# ESP32_EDITED.net
KiCad netlist of a schematic drawn in Altium Designer
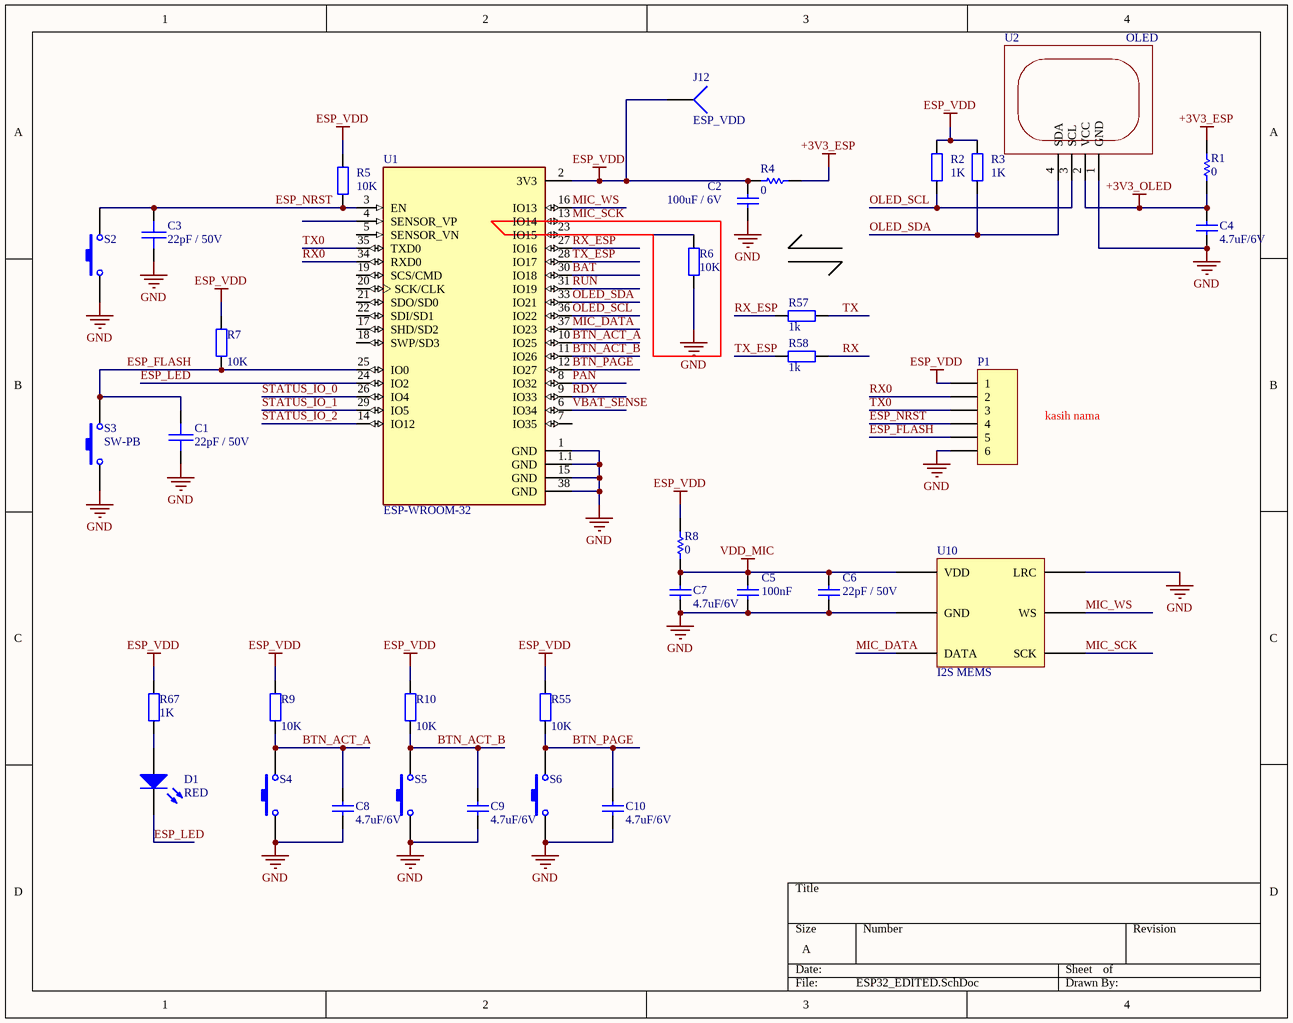
[diagram p0: ESP32_EDITED.SchDoc]

(export (version "E")
  (design (tool "Eeschema 10.0.6"))
  (components
    (comp (ref "C1")
      (value "22pF / 50V")
      (footprint "CR2012-0805")
      (description "Surface mount capacitor 0402")
      (libsource (lib "Vowstar_Basic_Device") (part "SMT_C_0402"))
    )
    (comp (ref "C2")
      (value "100uF / 6V")
      (footprint "CR3216-1206")
      (description "Capacitor")
      (fields (field (name "PUBLISHER") "Altium Limited"))
      (libsource (lib "Miscellaneous Devices") (part "Cap"))
    )
    (comp (ref "C3")
      (value "22pF / 50V")
      (footprint "CR2012-0805")
      (description "Surface mount capacitor 0402")
      (libsource (lib "Vowstar_Basic_Device") (part "SMT_C_0402"))
    )
    (comp (ref "C4")
      (value "4.7uF/6V")
      (footprint "CR2012-0805")
      (description "Capacitor (Semiconductor SIM Model)")
      (fields (field (name "PUBLISHER") "Altium Limited"))
      (libsource (lib "passive") (part "Cap Semi"))
    )
    (comp (ref "C5")
      (value "100nF")
      (footprint "CR2012-0805")
      (description "Capacitor")
      (fields (field (name "PUBLISHER") "Altium Limited"))
      (libsource (lib "Miscellaneous Devices") (part "Cap"))
    )
    (comp (ref "C6")
      (value "22pF / 50V")
      (footprint "CR2012-0805")
      (description "Capacitor")
      (fields (field (name "PUBLISHER") "Altium Limited"))
      (libsource (lib "Miscellaneous Devices") (part "Cap"))
    )
    (comp (ref "C7")
      (value "4.7uF/6V")
      (footprint "CR2012-0805")
      (description "Capacitor (Semiconductor SIM Model)")
      (fields (field (name "PUBLISHER") "Altium Limited"))
      (libsource (lib "passive") (part "Cap Semi"))
    )
    (comp (ref "C8")
      (value "4.7uF/6V")
      (footprint "CR2012-0805")
      (description "Capacitor (Semiconductor SIM Model)")
      (fields (field (name "PUBLISHER") "Altium Limited"))
      (libsource (lib "passive") (part "Cap Semi"))
    )
    (comp (ref "C9")
      (value "4.7uF/6V")
      (footprint "CR2012-0805")
      (description "Capacitor (Semiconductor SIM Model)")
      (fields (field (name "PUBLISHER") "Altium Limited"))
      (libsource (lib "passive") (part "Cap Semi"))
    )
    (comp (ref "C10")
      (value "4.7uF/6V")
      (footprint "CR2012-0805")
      (description "Capacitor (Semiconductor SIM Model)")
      (fields (field (name "PUBLISHER") "Altium Limited"))
      (libsource (lib "passive") (part "Cap Semi"))
    )
    (comp (ref "D1")
      (value "RED")
      (footprint "LED1206")
      (description "Typical RED, GREEN, YELLOW, AMBER GaAs LED")
      (fields (field (name "PUBLISHER") "Altium Limited"))
      (libsource (lib "Miscellaneous Devices") (part "LED2"))
    )
    (comp (ref "J12")
      (value "ESP_VDD")
      (footprint "PIN1")
      (description "Socket")
      (fields (field (name "PUBLISHER") "Altium Limited"))
      (libsource (lib "Miscellaneous Connectors") (part "Socket"))
    )
    (comp (ref "P1")
      (value "Header 6")
      (footprint "HDR1X6")
      (description "Header, 6-Pin")
      (fields (field (name "PUBLISHER") "Altium Limited"))
      (libsource (lib "Miscellaneous Connectors") (part "Header 6"))
    )
    (comp (ref "R1")
      (value "0")
      (footprint "JP1_SMD")
      (description "Semiconductor Resistor")
      (fields (field (name "PUBLISHER") "Altium Limited"))
      (libsource (lib "passive") (part "Res Semi"))
    )
    (comp (ref "R2")
      (value "1K")
      (footprint "CR2012-0805")
      (description "Resistor")
      (fields (field (name "PUBLISHER") "Altium Limited"))
      (libsource (lib "Miscellaneous Devices") (part "Res2"))
    )
    (comp (ref "R3")
      (value "1K")
      (footprint "CR2012-0805")
      (description "Resistor")
      (fields (field (name "PUBLISHER") "Altium Limited"))
      (libsource (lib "Miscellaneous Devices") (part "Res2"))
    )
    (comp (ref "R4")
      (value "0")
      (footprint "JP1_SMD")
      (description "Semiconductor Resistor")
      (fields (field (name "PUBLISHER") "Altium Limited"))
      (libsource (lib "passive") (part "Res Semi"))
    )
    (comp (ref "R5")
      (value "10K")
      (footprint "CR2012-0805")
      (description "Resistor")
      (fields (field (name "PUBLISHER") "Altium Limited"))
      (libsource (lib "Miscellaneous Devices") (part "Res2"))
    )
    (comp (ref "R6")
      (value "10K")
      (footprint "CR2012-0805")
      (description "Resistor")
      (fields (field (name "PUBLISHER") "Altium Limited"))
      (libsource (lib "") (part "Res2_2"))
    )
    (comp (ref "R7")
      (value "10K")
      (footprint "CR2012-0805")
      (description "Resistor")
      (fields (field (name "PUBLISHER") "Altium Limited"))
      (libsource (lib "Miscellaneous Devices") (part "Res2"))
    )
    (comp (ref "R8")
      (value "0")
      (footprint "JP1_SMD")
      (description "Semiconductor Resistor")
      (fields (field (name "PUBLISHER") "Altium Limited"))
      (libsource (lib "passive") (part "Res Semi"))
    )
    (comp (ref "R9")
      (value "10K")
      (footprint "CR2012-0805")
      (description "Resistor")
      (fields (field (name "PUBLISHER") "Altium Limited"))
      (libsource (lib "Miscellaneous Devices") (part "Res2"))
    )
    (comp (ref "R10")
      (value "10K")
      (footprint "CR2012-0805")
      (description "Resistor")
      (fields (field (name "PUBLISHER") "Altium Limited"))
      (libsource (lib "Miscellaneous Devices") (part "Res2"))
    )
    (comp (ref "R55")
      (value "10K")
      (footprint "CR2012-0805")
      (description "Resistor")
      (fields (field (name "PUBLISHER") "Altium Limited"))
      (libsource (lib "Miscellaneous Devices") (part "Res2"))
    )
    (comp (ref "R57")
      (value "1k")
      (footprint "CR2012-0805")
      (description "Resistor")
      (fields (field (name "PUBLISHER") "Altium Limited"))
      (libsource (lib "") (part "Res2_1"))
    )
    (comp (ref "R58")
      (value "1k")
      (footprint "CR2012-0805")
      (description "Resistor")
      (fields (field (name "PUBLISHER") "Altium Limited"))
      (libsource (lib "") (part "Res2_1"))
    )
    (comp (ref "R67")
      (value "1K")
      (footprint "CR2012-0805")
      (description "Resistor")
      (fields (field (name "PUBLISHER") "Altium Limited"))
      (libsource (lib "Miscellaneous Devices") (part "Res2"))
    )
    (comp (ref "S2")
      (value "SW-PB")
      (footprint "pushbutton")
      (description "Switch")
      (fields (field (name "PUBLISHER") "Altium Limited"))
      (libsource (lib "Miscellaneous Devices") (part "SW-PB"))
    )
    (comp (ref "S3") (value "SW-PB") (footprint "pushbutton") (libsource (lib "passive") (part "pushbutton")))
    (comp (ref "S4")
      (value "SW-PB")
      (footprint "pushbutton")
      (description "Switch")
      (fields (field (name "PUBLISHER") "Altium Limited"))
      (libsource (lib "Miscellaneous Devices") (part "SW-PB"))
    )
    (comp (ref "S5")
      (value "SW-PB")
      (footprint "pushbutton")
      (description "Switch")
      (fields (field (name "PUBLISHER") "Altium Limited"))
      (libsource (lib "Miscellaneous Devices") (part "SW-PB"))
    )
    (comp (ref "S6")
      (value "SW-PB")
      (footprint "pushbutton")
      (description "Switch")
      (fields (field (name "PUBLISHER") "Altium Limited"))
      (libsource (lib "Miscellaneous Devices") (part "SW-PB"))
    )
    (comp (ref "U1")
      (value "ESP-WROOM-32")
      (footprint "MODULE_ESP-WROOM-32")
      (description "WiFi 802.11b/g/n/d/e/i Transceiver Module 2.4GHz Surface Mount")
      (fields (field (name "MF") "Olimex LTD"))
      (libsource (lib "ESP-WROOM-32") (part "ESP-WROOM-32"))
    )
    (comp (ref "U2")
      (value "OLED")
      (footprint "OLED_Display_1in6")
      (description "I2C OLED 0.96\"")
      (libsource (lib "active") (part "OLED"))
    )
    (comp (ref "U10") (value "I2S MEMS") (footprint "INMP441") (libsource (lib "active") (part "INMP441")))
  )
  (nets
    (net (code "1") (name "+3V3_ESP") (class "Default")
      (node (ref "R1") (pin "2") (pinfunction "2_2") (pintype "passive"))
      (node (ref "R4") (pin "2") (pinfunction "2_2") (pintype "passive"))
    )
    (net (code "2") (name "+3V3_OLED") (class "Default")
      (node (ref "C4") (pin "2") (pinfunction "2_2") (pintype "passive"))
      (node (ref "R1") (pin "1") (pinfunction "1_1") (pintype "passive"))
      (node (ref "U2") (pin "2") (pinfunction "VCC_2") (pintype "passive"))
    )
    (net (code "3") (name "/BAT") (class "Default")
      (node (ref "U1") (pin "30") (pinfunction "IO18_30") (pintype "bidirectional"))
    )
    (net (code "4") (name "/BTN_ACT_A") (class "Default")
      (node (ref "C8") (pin "2") (pinfunction "2_2") (pintype "passive"))
      (node (ref "R9") (pin "1") (pinfunction "1_1") (pintype "passive"))
      (node (ref "S4") (pin "2") (pinfunction "2_2") (pintype "passive"))
      (node (ref "U1") (pin "10") (pinfunction "IO25_10") (pintype "bidirectional"))
    )
    (net (code "5") (name "/BTN_ACT_B") (class "Default")
      (node (ref "C9") (pin "2") (pinfunction "2_2") (pintype "passive"))
      (node (ref "R10") (pin "1") (pinfunction "1_1") (pintype "passive"))
      (node (ref "S5") (pin "2") (pinfunction "2_2") (pintype "passive"))
      (node (ref "U1") (pin "11") (pinfunction "IO26_11") (pintype "bidirectional"))
    )
    (net (code "6") (name "/BTN_PAGE") (class "Default")
      (node (ref "C10") (pin "2") (pinfunction "2_2") (pintype "passive"))
      (node (ref "R55") (pin "1") (pinfunction "1_1") (pintype "passive"))
      (node (ref "S6") (pin "2") (pinfunction "2_2") (pintype "passive"))
      (node (ref "U1") (pin "12") (pinfunction "IO27_12") (pintype "bidirectional"))
    )
    (net (code "7") (name "/ESP_FLASH") (class "Default")
      (node (ref "C1") (pin "1") (pinfunction "1_1") (pintype "passive"))
      (node (ref "P1") (pin "5") (pinfunction "5_5") (pintype "passive"))
      (node (ref "R7") (pin "1") (pinfunction "1_1") (pintype "passive"))
      (node (ref "S3") (pin "2") (pinfunction "2_2") (pintype "passive"))
      (node (ref "U1") (pin "25") (pinfunction "IO0_25") (pintype "bidirectional"))
    )
    (net (code "8") (name "/ESP_LED") (class "Default")
      (node (ref "D1") (pin "K") (pinfunction "K_K") (pintype "passive"))
      (node (ref "U1") (pin "24") (pinfunction "IO2_24") (pintype "bidirectional"))
    )
    (net (code "9") (name "/ESP_NRST") (class "Default")
      (node (ref "C3") (pin "1") (pinfunction "1_1") (pintype "passive"))
      (node (ref "P1") (pin "4") (pinfunction "4_4") (pintype "passive"))
      (node (ref "R5") (pin "1") (pinfunction "1_1") (pintype "passive"))
      (node (ref "S2") (pin "2") (pinfunction "2_2") (pintype "passive"))
      (node (ref "U1") (pin "3") (pinfunction "EN_3") (pintype "input"))
    )
    (net (code "10") (name "/MIC_DATA") (class "Default")
      (node (ref "U1") (pin "37") (pinfunction "IO23_37") (pintype "bidirectional"))
      (node (ref "U10") (pin "6") (pinfunction "DATA_6") (pintype "passive"))
    )
    (net (code "11") (name "/MIC_SCK") (class "Default")
      (node (ref "U1") (pin "13") (pinfunction "IO14_13") (pintype "bidirectional"))
      (node (ref "U10") (pin "1") (pinfunction "SCK_1") (pintype "passive"))
    )
    (net (code "12") (name "/MIC_WS") (class "Default")
      (node (ref "U1") (pin "16") (pinfunction "IO13_16") (pintype "bidirectional"))
      (node (ref "U10") (pin "2") (pinfunction "WS_2") (pintype "passive"))
    )
    (net (code "13") (name "/OLED_SCL") (class "Default")
      (node (ref "R2") (pin "1") (pinfunction "1_1") (pintype "passive"))
      (node (ref "U1") (pin "36") (pinfunction "IO22_36") (pintype "bidirectional"))
      (node (ref "U2") (pin "3") (pinfunction "SCL_3") (pintype "passive"))
    )
    (net (code "14") (name "/OLED_SDA") (class "Default")
      (node (ref "R3") (pin "1") (pinfunction "1_1") (pintype "passive"))
      (node (ref "U1") (pin "33") (pinfunction "IO21_33") (pintype "bidirectional"))
      (node (ref "U2") (pin "4") (pinfunction "SDA_4") (pintype "passive"))
    )
    (net (code "15") (name "/PAN") (class "Default")
      (node (ref "U1") (pin "8") (pinfunction "IO32_8") (pintype "bidirectional"))
    )
    (net (code "16") (name "/RDY") (class "Default")
      (node (ref "U1") (pin "9") (pinfunction "IO33_9") (pintype "bidirectional"))
    )
    (net (code "17") (name "/RUN") (class "Default")
      (node (ref "U1") (pin "31") (pinfunction "IO19_31") (pintype "bidirectional"))
    )
    (net (code "18") (name "/RX") (class "Default")
      (node (ref "R58") (pin "1") (pinfunction "1_1") (pintype "passive"))
    )
    (net (code "19") (name "/RX0") (class "Default")
      (node (ref "P1") (pin "2") (pinfunction "2_2") (pintype "passive"))
      (node (ref "U1") (pin "34") (pinfunction "RXD0_34") (pintype "bidirectional"))
    )
    (net (code "20") (name "/RX_ESP") (class "Default")
      (node (ref "R57") (pin "2") (pinfunction "2_2") (pintype "passive"))
      (node (ref "U1") (pin "27") (pinfunction "IO16_27") (pintype "bidirectional"))
    )
    (net (code "21") (name "/STATUS_IO_0") (class "Default")
      (node (ref "U1") (pin "26") (pinfunction "IO4_26") (pintype "bidirectional"))
    )
    (net (code "22") (name "/STATUS_IO_1") (class "Default")
      (node (ref "U1") (pin "29") (pinfunction "IO5_29") (pintype "bidirectional"))
    )
    (net (code "23") (name "/STATUS_IO_2") (class "Default")
      (node (ref "U1") (pin "14") (pinfunction "IO12_14") (pintype "bidirectional"))
    )
    (net (code "24") (name "/TX") (class "Default")
      (node (ref "R57") (pin "1") (pinfunction "1_1") (pintype "passive"))
    )
    (net (code "25") (name "/TX0") (class "Default")
      (node (ref "P1") (pin "3") (pinfunction "3_3") (pintype "passive"))
      (node (ref "U1") (pin "35") (pinfunction "TXD0_35") (pintype "bidirectional"))
    )
    (net (code "26") (name "/TX_ESP") (class "Default")
      (node (ref "R58") (pin "2") (pinfunction "2_2") (pintype "passive"))
      (node (ref "U1") (pin "28") (pinfunction "IO17_28") (pintype "bidirectional"))
    )
    (net (code "27") (name "/VBAT_SENSE") (class "Default")
      (node (ref "U1") (pin "6") (pinfunction "IO34_6") (pintype "bidirectional"))
    )
    (net (code "28") (name "ESP_VDD") (class "Default")
      (node (ref "C2") (pin "2") (pinfunction "2_2") (pintype "passive"))
      (node (ref "J12") (pin "1") (pinfunction "1_1") (pintype "passive"))
      (node (ref "P1") (pin "1") (pinfunction "1_1") (pintype "passive"))
      (node (ref "R10") (pin "2") (pinfunction "2_2") (pintype "passive"))
      (node (ref "R2") (pin "2") (pinfunction "2_2") (pintype "passive"))
      (node (ref "R3") (pin "2") (pinfunction "2_2") (pintype "passive"))
      (node (ref "R4") (pin "1") (pinfunction "1_1") (pintype "passive"))
      (node (ref "R5") (pin "2") (pinfunction "2_2") (pintype "passive"))
      (node (ref "R55") (pin "2") (pinfunction "2_2") (pintype "passive"))
      (node (ref "R67") (pin "2") (pinfunction "2_2") (pintype "passive"))
      (node (ref "R7") (pin "2") (pinfunction "2_2") (pintype "passive"))
      (node (ref "R8") (pin "1") (pinfunction "1_1") (pintype "passive"))
      (node (ref "R9") (pin "2") (pinfunction "2_2") (pintype "passive"))
      (node (ref "U1") (pin "2") (pinfunction "3V3_2") (pintype "power_in"))
    )
    (net (code "29") (name "GND") (class "Default")
      (node (ref "C1") (pin "2") (pinfunction "2_2") (pintype "passive"))
      (node (ref "C10") (pin "1") (pinfunction "1_1") (pintype "passive"))
      (node (ref "C2") (pin "1") (pinfunction "1_1") (pintype "passive"))
      (node (ref "C3") (pin "2") (pinfunction "2_2") (pintype "passive"))
      (node (ref "C4") (pin "1") (pinfunction "1_1") (pintype "passive"))
      (node (ref "C5") (pin "1") (pinfunction "1_1") (pintype "passive"))
      (node (ref "C6") (pin "1") (pinfunction "1_1") (pintype "passive"))
      (node (ref "C7") (pin "1") (pinfunction "1_1") (pintype "passive"))
      (node (ref "C8") (pin "1") (pinfunction "1_1") (pintype "passive"))
      (node (ref "C9") (pin "1") (pinfunction "1_1") (pintype "passive"))
      (node (ref "P1") (pin "6") (pinfunction "6_6") (pintype "passive"))
      (node (ref "R6") (pin "2") (pinfunction "2_2") (pintype "passive"))
      (node (ref "S2") (pin "1") (pinfunction "1_1") (pintype "passive"))
      (node (ref "S3") (pin "1") (pinfunction "1_1") (pintype "passive"))
      (node (ref "S4") (pin "1") (pinfunction "1_1") (pintype "passive"))
      (node (ref "S5") (pin "1") (pinfunction "1_1") (pintype "passive"))
      (node (ref "S6") (pin "1") (pinfunction "1_1") (pintype "passive"))
      (node (ref "U1") (pin "1") (pinfunction "GND_1") (pintype "power_in"))
      (node (ref "U1") (pin "1.1") (pinfunction "GND_1.1") (pintype "power_in"))
      (node (ref "U1") (pin "15") (pinfunction "GND_15") (pintype "power_in"))
      (node (ref "U1") (pin "38") (pinfunction "GND_38") (pintype "power_in"))
      (node (ref "U10") (pin "3") (pinfunction "LRC_3") (pintype "passive"))
      (node (ref "U10") (pin "4") (pinfunction "GND_4") (pintype "power_in"))
      (node (ref "U2") (pin "1") (pinfunction "GND_1") (pintype "passive"))
    )
    (net (code "30") (name "Net-(D1-PadA)") (class "Default")
      (node (ref "D1") (pin "A") (pinfunction "A_A") (pintype "passive"))
      (node (ref "R67") (pin "1") (pinfunction "1_1") (pintype "passive"))
    )
    (net (code "31") (name "Net-(U1-IO15)") (class "Default")
      (node (ref "R6") (pin "1") (pinfunction "1_1") (pintype "passive"))
      (node (ref "U1") (pin "23") (pinfunction "IO15_23") (pintype "bidirectional"))
    )
    (net (code "32") (name "VDD_MIC") (class "Default")
      (node (ref "C5") (pin "2") (pinfunction "2_2") (pintype "passive"))
      (node (ref "C6") (pin "2") (pinfunction "2_2") (pintype "passive"))
      (node (ref "C7") (pin "2") (pinfunction "2_2") (pintype "passive"))
      (node (ref "R8") (pin "2") (pinfunction "2_2") (pintype "passive"))
      (node (ref "U10") (pin "5") (pinfunction "VDD_5") (pintype "power_in"))
    )
    (net (code "33") (name "unconnected-(U1-IO35-Pad7)") (class "Default")
      (node (ref "U1") (pin "7") (pinfunction "IO35_7") (pintype "bidirectional"))
    )
    (net (code "34") (name "unconnected-(U1-SCK{slash}CLK-Pad20)") (class "Default")
      (node (ref "U1") (pin "20") (pinfunction "SCK/CLK_20") (pintype "bidirectional"))
    )
    (net (code "35") (name "unconnected-(U1-SCS{slash}CMD-Pad19)") (class "Default")
      (node (ref "U1") (pin "19") (pinfunction "SCS/CMD_19") (pintype "bidirectional"))
    )
    (net (code "36") (name "unconnected-(U1-SDI{slash}SD1-Pad22)") (class "Default")
      (node (ref "U1") (pin "22") (pinfunction "SDI/SD1_22") (pintype "bidirectional"))
    )
    (net (code "37") (name "unconnected-(U1-SDO{slash}SD0-Pad21)") (class "Default")
      (node (ref "U1") (pin "21") (pinfunction "SDO/SD0_21") (pintype "bidirectional"))
    )
    (net (code "38") (name "unconnected-(U1-SENSOR_VN-Pad5)") (class "Default")
      (node (ref "U1") (pin "5") (pinfunction "SENSOR_VN_5") (pintype "input"))
    )
    (net (code "39") (name "unconnected-(U1-SENSOR_VP-Pad4)") (class "Default")
      (node (ref "U1") (pin "4") (pinfunction "SENSOR_VP_4") (pintype "input"))
    )
    (net (code "40") (name "unconnected-(U1-SHD{slash}SD2-Pad17)") (class "Default")
      (node (ref "U1") (pin "17") (pinfunction "SHD/SD2_17") (pintype "bidirectional"))
    )
    (net (code "41") (name "unconnected-(U1-SWP{slash}SD3-Pad18)") (class "Default")
      (node (ref "U1") (pin "18") (pinfunction "SWP/SD3_18") (pintype "bidirectional"))
    )
  )
)
